# Power_Board.net
KiCad netlist of a schematic drawn in EAGLE
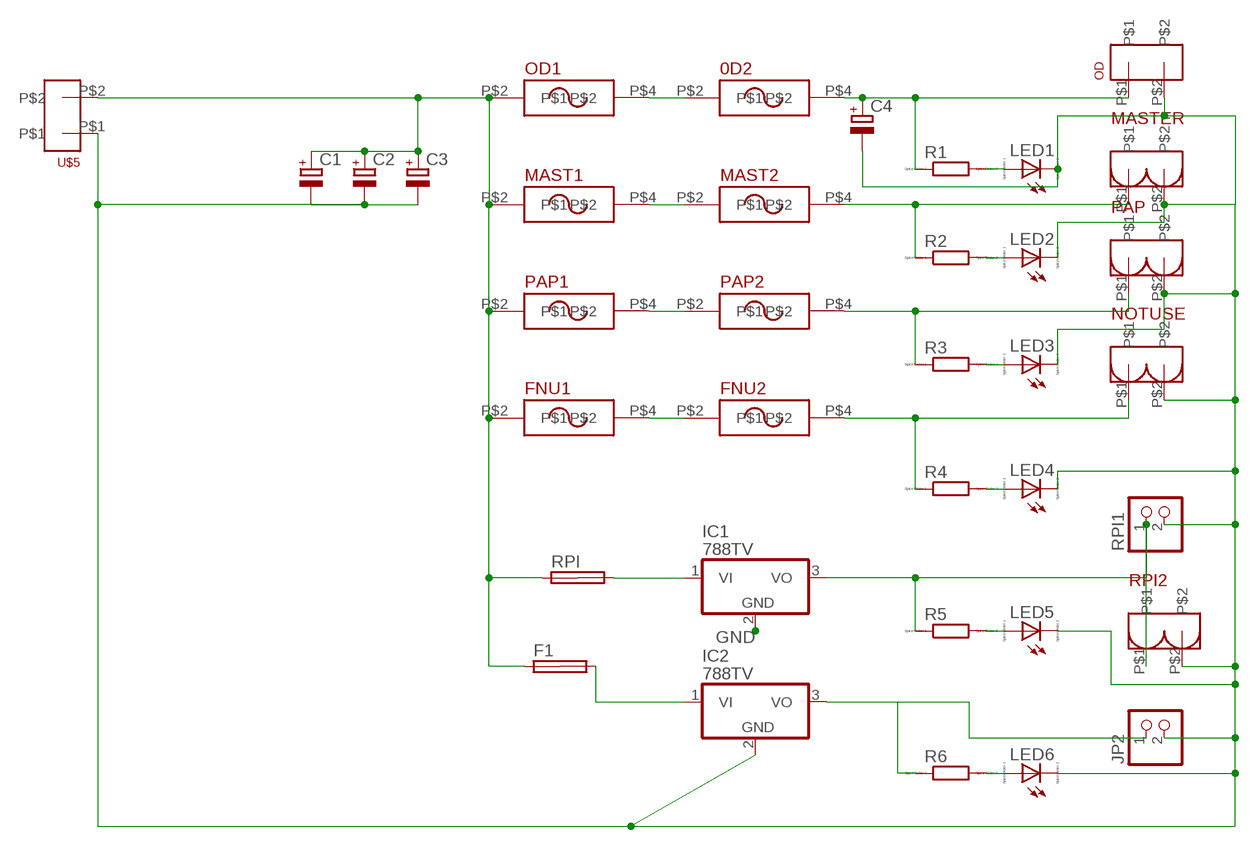
[diagram p0: schematic, sheet 1]

(export (version "E")
  (design (tool "Eeschema 10.0.6"))
  (components
    (comp (ref "0D2")
      (value "AUTO_FUSE")
      (footprint "eagle-import:AUTO_FUSE")
      (libsource (lib "eagle-import") (part "AUTO_FUSE"))
    )
    (comp (ref "C1")
      (value "CPOL-EUE7.5-18")
      (footprint "eagle-import:E7,5-18")
      (libsource (lib "eagle-import") (part "CPOL-EUE7.5-18"))
    )
    (comp (ref "C2")
      (value "CPOL-EUE7.5-18")
      (footprint "eagle-import:E7,5-18")
      (libsource (lib "eagle-import") (part "CPOL-EUE7.5-18"))
    )
    (comp (ref "C3")
      (value "CPOL-EUE7.5-18")
      (footprint "eagle-import:E7,5-18")
      (libsource (lib "eagle-import") (part "CPOL-EUE7.5-18"))
    )
    (comp (ref "C4")
      (value "CPOL-EUE5-13")
      (footprint "eagle-import:E5-13")
      (libsource (lib "eagle-import") (part "CPOL-EUE5-13"))
    )
    (comp (ref "F1")
      (value "SHK20L")
      (footprint "eagle-import:SHK20L")
      (libsource (lib "eagle-import") (part "SHK20L"))
    )
    (comp (ref "FNU1")
      (value "AUTO_FUSE")
      (footprint "eagle-import:AUTO_FUSE")
      (libsource (lib "eagle-import") (part "AUTO_FUSE"))
    )
    (comp (ref "FNU2")
      (value "AUTO_FUSE")
      (footprint "eagle-import:AUTO_FUSE")
      (libsource (lib "eagle-import") (part "AUTO_FUSE"))
    )
    (comp (ref "IC1")
      (value "788TV")
      (footprint "eagle-import:TO220V")
      (libsource (lib "eagle-import") (part "78TV8"))
    )
    (comp (ref "IC2")
      (value "788TV")
      (footprint "eagle-import:TO220V")
      (libsource (lib "eagle-import") (part "78TV8"))
    )
    (comp (ref "JP2")
      (value "PINHD-1X2")
      (footprint "eagle-import:1X02")
      (libsource (lib "eagle-import") (part "PINHD-1X2"))
    )
    (comp (ref "LED1")
      (value "LED_ELD260")
      (footprint "eagle-import:LED_LD260")
      (libsource (lib "eagle-import") (part "LED_ELD260"))
    )
    (comp (ref "LED2")
      (value "LED_ELD260")
      (footprint "eagle-import:LED_LD260")
      (libsource (lib "eagle-import") (part "LED_ELD260"))
    )
    (comp (ref "LED3")
      (value "LED_ELD260")
      (footprint "eagle-import:LED_LD260")
      (libsource (lib "eagle-import") (part "LED_ELD260"))
    )
    (comp (ref "LED4")
      (value "LED_ELD260")
      (footprint "eagle-import:LED_LD260")
      (libsource (lib "eagle-import") (part "LED_ELD260"))
    )
    (comp (ref "LED5")
      (value "LED_ELD260")
      (footprint "eagle-import:LED_LD260")
      (libsource (lib "eagle-import") (part "LED_ELD260"))
    )
    (comp (ref "LED6")
      (value "LED_ELD260")
      (footprint "eagle-import:LED_LD260")
      (libsource (lib "eagle-import") (part "LED_ELD260"))
    )
    (comp (ref "MAST1")
      (value "AUTO_FUSE")
      (footprint "eagle-import:AUTO_FUSE")
      (libsource (lib "eagle-import") (part "AUTO_FUSE"))
    )
    (comp (ref "MAST2")
      (value "AUTO_FUSE")
      (footprint "eagle-import:AUTO_FUSE")
      (libsource (lib "eagle-import") (part "AUTO_FUSE"))
    )
    (comp (ref "MASTER")
      (value "GREEN_HEADER")
      (footprint "eagle-import:GREEN_HEADER")
      (libsource (lib "eagle-import") (part "GREEN_HEADER"))
    )
    (comp (ref "NOTUSE")
      (value "GREEN_HEADER")
      (footprint "eagle-import:GREEN_HEADER")
      (libsource (lib "eagle-import") (part "GREEN_HEADER"))
    )
    (comp (ref "OD")
      (value "3MM_HEADER_2")
      (footprint "eagle-import:3MM_HEADER_2")
      (libsource (lib "eagle-import") (part "3MM_HEADER_2"))
    )
    (comp (ref "OD1")
      (value "AUTO_FUSE")
      (footprint "eagle-import:AUTO_FUSE")
      (libsource (lib "eagle-import") (part "AUTO_FUSE"))
    )
    (comp (ref "PAP")
      (value "GREEN_HEADER")
      (footprint "eagle-import:GREEN_HEADER")
      (libsource (lib "eagle-import") (part "GREEN_HEADER"))
    )
    (comp (ref "PAP1")
      (value "AUTO_FUSE")
      (footprint "eagle-import:AUTO_FUSE")
      (libsource (lib "eagle-import") (part "AUTO_FUSE"))
    )
    (comp (ref "PAP2")
      (value "AUTO_FUSE")
      (footprint "eagle-import:AUTO_FUSE")
      (libsource (lib "eagle-import") (part "AUTO_FUSE"))
    )
    (comp (ref "R1")
      (value "R0207/10")
      (footprint "eagle-import:0207_10")
      (libsource (lib "eagle-import") (part "R0207/10"))
    )
    (comp (ref "R2")
      (value "R0207/10")
      (footprint "eagle-import:0207_10")
      (libsource (lib "eagle-import") (part "R0207/10"))
    )
    (comp (ref "R3")
      (value "R0207/10")
      (footprint "eagle-import:0207_10")
      (libsource (lib "eagle-import") (part "R0207/10"))
    )
    (comp (ref "R4")
      (value "R0207/10")
      (footprint "eagle-import:0207_10")
      (libsource (lib "eagle-import") (part "R0207/10"))
    )
    (comp (ref "R5")
      (value "R0207/10")
      (footprint "eagle-import:0207_10")
      (libsource (lib "eagle-import") (part "R0207/10"))
    )
    (comp (ref "R6")
      (value "R0207/10")
      (footprint "eagle-import:0207_10")
      (libsource (lib "eagle-import") (part "R0207/10"))
    )
    (comp (ref "RPI")
      (value "SHK20L")
      (footprint "eagle-import:SHK20L")
      (libsource (lib "eagle-import") (part "SHK20L"))
    )
    (comp (ref "RPI1")
      (value "PINHD-1X2")
      (footprint "eagle-import:1X02")
      (libsource (lib "eagle-import") (part "PINHD-1X2"))
    )
    (comp (ref "RPI2")
      (value "GREEN_HEADER")
      (footprint "eagle-import:GREEN_HEADER")
      (libsource (lib "eagle-import") (part "GREEN_HEADER"))
    )
    (comp (ref "U$5")
      (value "3MM_HEADER_2")
      (footprint "eagle-import:3MM_HEADER_2")
      (libsource (lib "eagle-import") (part "3MM_HEADER_2"))
    )
  )
  (nets
    (net (code "1") (name "/GND") (class "Default")
      (node (ref "C1") (pin "-") (pinfunction "-_-") (pintype "passive"))
      (node (ref "C2") (pin "-") (pinfunction "-_-") (pintype "passive"))
      (node (ref "C3") (pin "-") (pinfunction "-_-") (pintype "passive"))
      (node (ref "C4") (pin "-") (pinfunction "-_-") (pintype "passive"))
      (node (ref "IC1") (pin "2") (pinfunction "GND_2") (pintype "passive"))
      (node (ref "IC2") (pin "2") (pinfunction "GND_2") (pintype "passive"))
      (node (ref "JP2") (pin "2") (pinfunction "2_2") (pintype "passive"))
      (node (ref "LED1") (pin "K") (pinfunction "C_K") (pintype "passive"))
      (node (ref "LED2") (pin "K") (pinfunction "C_K") (pintype "passive"))
      (node (ref "LED3") (pin "K") (pinfunction "C_K") (pintype "passive"))
      (node (ref "LED4") (pin "K") (pinfunction "C_K") (pintype "passive"))
      (node (ref "LED5") (pin "K") (pinfunction "C_K") (pintype "passive"))
      (node (ref "LED6") (pin "K") (pinfunction "C_K") (pintype "passive"))
      (node (ref "MASTER") (pin "P$2") (pinfunction "P$2_P$2") (pintype "bidirectional"))
      (node (ref "NOTUSE") (pin "P$2") (pinfunction "P$2_P$2") (pintype "bidirectional"))
      (node (ref "OD") (pin "P$2") (pinfunction "P$2_P$2") (pintype "bidirectional"))
      (node (ref "PAP") (pin "P$2") (pinfunction "P$2_P$2") (pintype "bidirectional"))
      (node (ref "RPI1") (pin "2") (pinfunction "2_2") (pintype "passive"))
      (node (ref "RPI2") (pin "P$2") (pinfunction "P$2_P$2") (pintype "bidirectional"))
      (node (ref "U$5") (pin "P$1") (pinfunction "P$1_P$1") (pintype "bidirectional"))
    )
    (net (code "2") (name "Net-(0D2-P$1)") (class "Default")
      (node (ref "0D2") (pin "P$2") (pinfunction "P$1_P$2") (pintype "bidirectional"))
      (node (ref "OD1") (pin "P$4") (pinfunction "P$2_P$4") (pintype "bidirectional"))
    )
    (net (code "3") (name "Net-(0D2-P$2)") (class "Default")
      (node (ref "0D2") (pin "P$4") (pinfunction "P$2_P$4") (pintype "bidirectional"))
      (node (ref "C4") (pin "+") (pinfunction "+_+") (pintype "passive"))
      (node (ref "OD") (pin "P$1") (pinfunction "P$1_P$1") (pintype "bidirectional"))
      (node (ref "R1") (pin "1") (pinfunction "1_1") (pintype "passive"))
    )
    (net (code "4") (name "Net-(FNU1-P$1)") (class "Default")
      (node (ref "C1") (pin "+") (pinfunction "+_+") (pintype "passive"))
      (node (ref "C2") (pin "+") (pinfunction "+_+") (pintype "passive"))
      (node (ref "C3") (pin "+") (pinfunction "+_+") (pintype "passive"))
      (node (ref "F1") (pin "1A") (pinfunction "1A_1A") (pintype "passive"))
      (node (ref "FNU1") (pin "P$2") (pinfunction "P$1_P$2") (pintype "bidirectional"))
      (node (ref "MAST1") (pin "P$2") (pinfunction "P$1_P$2") (pintype "bidirectional"))
      (node (ref "OD1") (pin "P$2") (pinfunction "P$1_P$2") (pintype "bidirectional"))
      (node (ref "PAP1") (pin "P$2") (pinfunction "P$1_P$2") (pintype "bidirectional"))
      (node (ref "RPI") (pin "1A") (pinfunction "1A_1A") (pintype "passive"))
      (node (ref "U$5") (pin "P$2") (pinfunction "P$2_P$2") (pintype "bidirectional"))
    )
    (net (code "5") (name "Net-(FNU1-P$2)") (class "Default")
      (node (ref "FNU1") (pin "P$4") (pinfunction "P$2_P$4") (pintype "bidirectional"))
      (node (ref "FNU2") (pin "P$2") (pinfunction "P$1_P$2") (pintype "bidirectional"))
    )
    (net (code "6") (name "Net-(FNU2-P$2)") (class "Default")
      (node (ref "FNU2") (pin "P$4") (pinfunction "P$2_P$4") (pintype "bidirectional"))
      (node (ref "NOTUSE") (pin "P$1") (pinfunction "P$1_P$1") (pintype "bidirectional"))
      (node (ref "R4") (pin "1") (pinfunction "1_1") (pintype "passive"))
    )
    (net (code "7") (name "Net-(IC1-VI)") (class "Default")
      (node (ref "IC1") (pin "1") (pinfunction "VI_1") (pintype "input"))
      (node (ref "RPI") (pin "2A") (pinfunction "2A_2A") (pintype "passive"))
    )
    (net (code "8") (name "Net-(IC1-VO)") (class "Default")
      (node (ref "IC1") (pin "3") (pinfunction "VO_3") (pintype "passive"))
      (node (ref "R5") (pin "1") (pinfunction "1_1") (pintype "passive"))
      (node (ref "RPI1") (pin "1") (pinfunction "1_1") (pintype "passive"))
      (node (ref "RPI2") (pin "P$1") (pinfunction "P$1_P$1") (pintype "bidirectional"))
    )
    (net (code "9") (name "Net-(IC2-VI)") (class "Default")
      (node (ref "F1") (pin "2A") (pinfunction "2A_2A") (pintype "passive"))
      (node (ref "IC2") (pin "1") (pinfunction "VI_1") (pintype "input"))
    )
    (net (code "10") (name "Net-(IC2-VO)") (class "Default")
      (node (ref "IC2") (pin "3") (pinfunction "VO_3") (pintype "passive"))
      (node (ref "JP2") (pin "1") (pinfunction "1_1") (pintype "passive"))
      (node (ref "R6") (pin "1") (pinfunction "1_1") (pintype "passive"))
    )
    (net (code "11") (name "Net-(LED1-PadA)") (class "Default")
      (node (ref "LED1") (pin "A") (pinfunction "A_A") (pintype "passive"))
      (node (ref "R1") (pin "2") (pinfunction "2_2") (pintype "passive"))
    )
    (net (code "12") (name "Net-(LED2-PadA)") (class "Default")
      (node (ref "LED2") (pin "A") (pinfunction "A_A") (pintype "passive"))
      (node (ref "R2") (pin "2") (pinfunction "2_2") (pintype "passive"))
    )
    (net (code "13") (name "Net-(LED3-PadA)") (class "Default")
      (node (ref "LED3") (pin "A") (pinfunction "A_A") (pintype "passive"))
      (node (ref "R3") (pin "2") (pinfunction "2_2") (pintype "passive"))
    )
    (net (code "14") (name "Net-(LED4-PadA)") (class "Default")
      (node (ref "LED4") (pin "A") (pinfunction "A_A") (pintype "passive"))
      (node (ref "R4") (pin "2") (pinfunction "2_2") (pintype "passive"))
    )
    (net (code "15") (name "Net-(LED5-PadA)") (class "Default")
      (node (ref "LED5") (pin "A") (pinfunction "A_A") (pintype "passive"))
      (node (ref "R5") (pin "2") (pinfunction "2_2") (pintype "passive"))
    )
    (net (code "16") (name "Net-(LED6-PadA)") (class "Default")
      (node (ref "LED6") (pin "A") (pinfunction "A_A") (pintype "passive"))
      (node (ref "R6") (pin "2") (pinfunction "2_2") (pintype "passive"))
    )
    (net (code "17") (name "Net-(MAST1-P$2)") (class "Default")
      (node (ref "MAST1") (pin "P$4") (pinfunction "P$2_P$4") (pintype "bidirectional"))
      (node (ref "MAST2") (pin "P$2") (pinfunction "P$1_P$2") (pintype "bidirectional"))
    )
    (net (code "18") (name "Net-(MAST2-P$2)") (class "Default")
      (node (ref "MAST2") (pin "P$4") (pinfunction "P$2_P$4") (pintype "bidirectional"))
      (node (ref "MASTER") (pin "P$1") (pinfunction "P$1_P$1") (pintype "bidirectional"))
      (node (ref "R2") (pin "1") (pinfunction "1_1") (pintype "passive"))
    )
    (net (code "19") (name "Net-(PAP1-P$2)") (class "Default")
      (node (ref "PAP1") (pin "P$4") (pinfunction "P$2_P$4") (pintype "bidirectional"))
      (node (ref "PAP2") (pin "P$2") (pinfunction "P$1_P$2") (pintype "bidirectional"))
    )
    (net (code "20") (name "Net-(PAP2-P$2)") (class "Default")
      (node (ref "PAP") (pin "P$1") (pinfunction "P$1_P$1") (pintype "bidirectional"))
      (node (ref "PAP2") (pin "P$4") (pinfunction "P$2_P$4") (pintype "bidirectional"))
      (node (ref "R3") (pin "1") (pinfunction "1_1") (pintype "passive"))
    )
    (net (code "21") (name "unconnected-(F1-Pad1B)") (class "Default")
      (node (ref "F1") (pin "1B") (pinfunction "1B_1B") (pintype "passive"))
    )
    (net (code "22") (name "unconnected-(F1-Pad2B)") (class "Default")
      (node (ref "F1") (pin "2B") (pinfunction "2B_2B") (pintype "passive"))
    )
    (net (code "23") (name "unconnected-(RPI-Pad1B)") (class "Default")
      (node (ref "RPI") (pin "1B") (pinfunction "1B_1B") (pintype "passive"))
    )
    (net (code "24") (name "unconnected-(RPI-Pad2B)") (class "Default")
      (node (ref "RPI") (pin "2B") (pinfunction "2B_2B") (pintype "passive"))
    )
  )
)
